# SNES_MultiOut_2.net
KiCad netlist of a schematic drawn in EAGLE
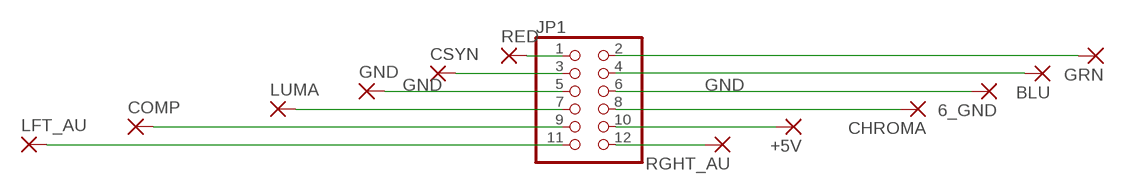
[diagram p0: schematic, sheet 1]

(export (version "E")
  (design (tool "Eeschema 10.0.6"))
  (components
    (comp (ref "+5V")
      (value "SMD2")
      (footprint "eagle-import:SMD1,27-2,54")
      (libsource (lib "eagle-import") (part "SMD2"))
    )
    (comp (ref "6_GND")
      (value "SMD2")
      (footprint "eagle-import:SMD1,27-2,54")
      (libsource (lib "eagle-import") (part "SMD2"))
    )
    (comp (ref "BLU")
      (value "SMD2")
      (footprint "eagle-import:SMD1,27-2,54")
      (libsource (lib "eagle-import") (part "SMD2"))
    )
    (comp (ref "CHROMA")
      (value "SMD2")
      (footprint "eagle-import:SMD1,27-2,54")
      (libsource (lib "eagle-import") (part "SMD2"))
    )
    (comp (ref "COMP")
      (value "SMD2")
      (footprint "eagle-import:SMD1,27-2,54")
      (libsource (lib "eagle-import") (part "SMD2"))
    )
    (comp (ref "CSYN")
      (value "SMD2")
      (footprint "eagle-import:SMD1,27-2,54")
      (libsource (lib "eagle-import") (part "SMD2"))
    )
    (comp (ref "GND")
      (value "SMD2")
      (footprint "eagle-import:SMD1,27-2,54")
      (libsource (lib "eagle-import") (part "SMD2"))
    )
    (comp (ref "GRN")
      (value "SMD2")
      (footprint "eagle-import:SMD1,27-2,54")
      (libsource (lib "eagle-import") (part "SMD2"))
    )
    (comp (ref "JP1")
      (value "PINHD-2X06_2.54")
      (footprint "eagle-import:2X06")
      (libsource (lib "eagle-import") (part "PINHD-2X06_2.54"))
    )
    (comp (ref "LFT_AU")
      (value "SMD2")
      (footprint "eagle-import:SMD1,27-2,54")
      (libsource (lib "eagle-import") (part "SMD2"))
    )
    (comp (ref "LUMA")
      (value "SMD2")
      (footprint "eagle-import:SMD1,27-2,54")
      (libsource (lib "eagle-import") (part "SMD2"))
    )
    (comp (ref "RED")
      (value "SMD2")
      (footprint "eagle-import:SMD1,27-2,54")
      (libsource (lib "eagle-import") (part "SMD2"))
    )
    (comp (ref "RGHT_AU")
      (value "SMD2")
      (footprint "eagle-import:SMD1,27-2,54")
      (libsource (lib "eagle-import") (part "SMD2"))
    )
  )
  (nets
    (net (code "1") (name "/GND") (class "Default")
      (node (ref "6_GND") (pin "1") (pinfunction "P_1") (pintype "passive"))
      (node (ref "GND") (pin "1") (pinfunction "P_1") (pintype "passive"))
      (node (ref "JP1") (pin "5") (pinfunction "5_5") (pintype "passive"))
      (node (ref "JP1") (pin "6") (pinfunction "6_6") (pintype "passive"))
    )
    (net (code "2") (name "Net-(+5V-P)") (class "Default")
      (node (ref "+5V") (pin "1") (pinfunction "P_1") (pintype "passive"))
      (node (ref "JP1") (pin "10") (pinfunction "10_10") (pintype "passive"))
    )
    (net (code "3") (name "Net-(BLU-P)") (class "Default")
      (node (ref "BLU") (pin "1") (pinfunction "P_1") (pintype "passive"))
      (node (ref "JP1") (pin "4") (pinfunction "4_4") (pintype "passive"))
    )
    (net (code "4") (name "Net-(CHROMA-P)") (class "Default")
      (node (ref "CHROMA") (pin "1") (pinfunction "P_1") (pintype "passive"))
      (node (ref "JP1") (pin "8") (pinfunction "8_8") (pintype "passive"))
    )
    (net (code "5") (name "Net-(COMP-P)") (class "Default")
      (node (ref "COMP") (pin "1") (pinfunction "P_1") (pintype "passive"))
      (node (ref "JP1") (pin "9") (pinfunction "9_9") (pintype "passive"))
    )
    (net (code "6") (name "Net-(CSYN-P)") (class "Default")
      (node (ref "CSYN") (pin "1") (pinfunction "P_1") (pintype "passive"))
      (node (ref "JP1") (pin "3") (pinfunction "3_3") (pintype "passive"))
    )
    (net (code "7") (name "Net-(GRN-P)") (class "Default")
      (node (ref "GRN") (pin "1") (pinfunction "P_1") (pintype "passive"))
      (node (ref "JP1") (pin "2") (pinfunction "2_2") (pintype "passive"))
    )
    (net (code "8") (name "Net-(LFT_AU-P)") (class "Default")
      (node (ref "JP1") (pin "11") (pinfunction "11_11") (pintype "passive"))
      (node (ref "LFT_AU") (pin "1") (pinfunction "P_1") (pintype "passive"))
    )
    (net (code "9") (name "Net-(LUMA-P)") (class "Default")
      (node (ref "JP1") (pin "7") (pinfunction "7_7") (pintype "passive"))
      (node (ref "LUMA") (pin "1") (pinfunction "P_1") (pintype "passive"))
    )
    (net (code "10") (name "Net-(RED-P)") (class "Default")
      (node (ref "JP1") (pin "1") (pinfunction "1_1") (pintype "passive"))
      (node (ref "RED") (pin "1") (pinfunction "P_1") (pintype "passive"))
    )
    (net (code "11") (name "Net-(RGHT_AU-P)") (class "Default")
      (node (ref "JP1") (pin "12") (pinfunction "12_12") (pintype "passive"))
      (node (ref "RGHT_AU") (pin "1") (pinfunction "P_1") (pintype "passive"))
    )
  )
)
